# JF-SV-LP0001.net
KiCad netlist of a schematic drawn in EAGLE
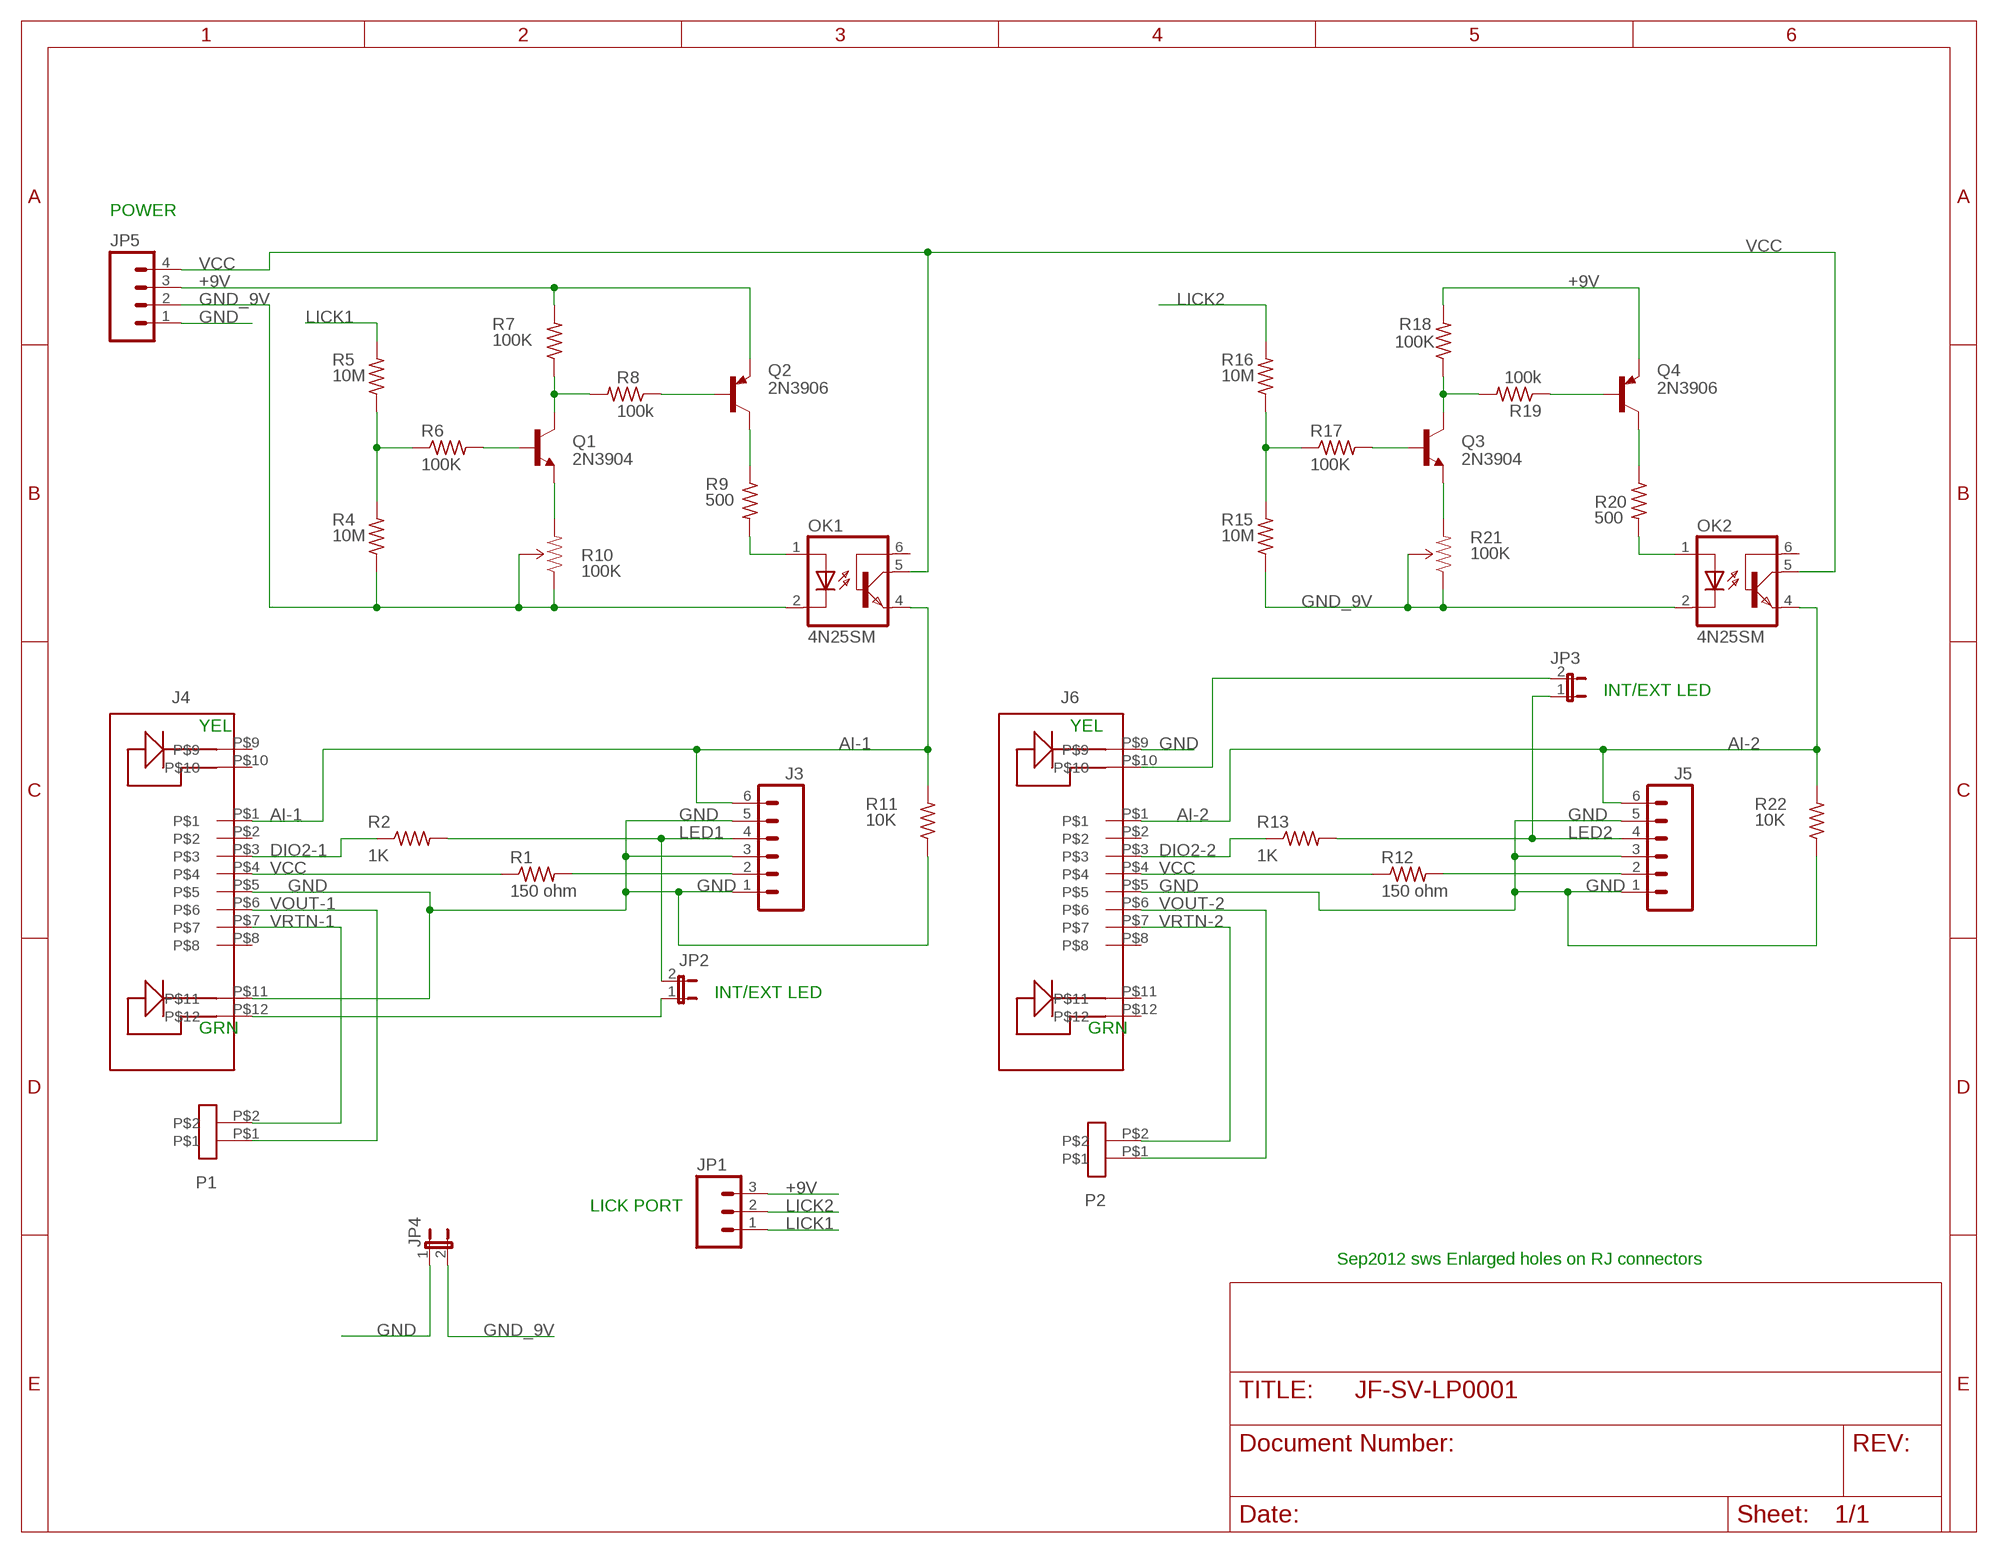
[diagram p0: schematic, sheet 1]

(export (version "E")
  (design (tool "Eeschema 10.0.6"))
  (components
    (comp (ref "J3")
      (value "M063.5MM-6")
      (footprint "eagle-import:SCREWTERMINAL-3.5MM-6")
      (libsource (lib "eagle-import") (part "M063.5MM-6"))
    )
    (comp (ref "J4")
      (value "RJ45_LED")
      (footprint "eagle-import:RJ45_LED")
      (libsource (lib "eagle-import") (part "RJ45_LED"))
    )
    (comp (ref "J5")
      (value "M063.5MM-6")
      (footprint "eagle-import:SCREWTERMINAL-3.5MM-6")
      (libsource (lib "eagle-import") (part "M063.5MM-6"))
    )
    (comp (ref "J6")
      (value "RJ45_LED")
      (footprint "eagle-import:RJ45_LED")
      (libsource (lib "eagle-import") (part "RJ45_LED"))
    )
    (comp (ref "JP1")
      (value "M03POLAR")
      (footprint "eagle-import:MOLEX-1X3")
      (libsource (lib "eagle-import") (part "M03POLAR"))
    )
    (comp (ref "JP2")
      (value "JP1E")
      (footprint "eagle-import:JP1")
      (libsource (lib "eagle-import") (part "JP1E"))
    )
    (comp (ref "JP3")
      (value "JP1E")
      (footprint "eagle-import:JP1")
      (libsource (lib "eagle-import") (part "JP1E"))
    )
    (comp (ref "JP4")
      (value "JUMPER-2PTH")
      (footprint "eagle-import:1X02")
      (libsource (lib "eagle-import") (part "JUMPER-2PTH"))
    )
    (comp (ref "JP5")
      (value "M04POLAR")
      (footprint "eagle-import:MOLEX-1X4")
      (libsource (lib "eagle-import") (part "M04POLAR"))
    )
    (comp (ref "OK1")
      (value "4N25SM")
      (footprint "eagle-import:DIL6-SMD")
      (fields (field (name "MF") "FAIRCHILD SEMICONDUCTOR"))
      (libsource (lib "eagle-import") (part "4N?MS25"))
    )
    (comp (ref "OK2")
      (value "4N25SM")
      (footprint "eagle-import:DIL6-SMD")
      (fields (field (name "MF") "FAIRCHILD SEMICONDUCTOR"))
      (libsource (lib "eagle-import") (part "4N?MS25"))
    )
    (comp (ref "P1")
      (value "CON2MICRO-FIT")
      (footprint "eagle-import:MICRO-FIT-2-RA")
      (libsource (lib "eagle-import") (part "CON2MICRO-FIT"))
    )
    (comp (ref "P2")
      (value "CON2MICRO-FIT")
      (footprint "eagle-import:MICRO-FIT-2-RA")
      (libsource (lib "eagle-import") (part "CON2MICRO-FIT"))
    )
    (comp (ref "Q1")
      (value "2N3904")
      (footprint "eagle-import:SOT23-BEC")
      (libsource (lib "eagle-import") (part "-NPN-SOT23-BECMMBT3904LT1"))
    )
    (comp (ref "Q2")
      (value "2N3906")
      (footprint "eagle-import:SOT23-BEC")
      (libsource (lib "eagle-import") (part "-PNP-SOT23-BECMMBT3906LT1"))
    )
    (comp (ref "Q3")
      (value "2N3904")
      (footprint "eagle-import:SOT23-BEC")
      (libsource (lib "eagle-import") (part "-NPN-SOT23-BECMMBT3904LT1"))
    )
    (comp (ref "Q4")
      (value "2N3906")
      (footprint "eagle-import:SOT23-BEC")
      (libsource (lib "eagle-import") (part "-PNP-SOT23-BECMMBT3906LT1"))
    )
    (comp (ref "R1")
      (value "150 ohm")
      (footprint "eagle-import:0805S")
      (libsource (lib "eagle-import") (part "RESISTOR_SM0805S"))
    )
    (comp (ref "R2")
      (value "1K")
      (footprint "eagle-import:0805S")
      (libsource (lib "eagle-import") (part "RESISTOR_SM0805S"))
    )
    (comp (ref "R4")
      (value "10M")
      (footprint "eagle-import:0805S")
      (libsource (lib "eagle-import") (part "RESISTOR_SM0805S"))
    )
    (comp (ref "R5")
      (value "10M")
      (footprint "eagle-import:0805S")
      (libsource (lib "eagle-import") (part "RESISTOR_SM0805S"))
    )
    (comp (ref "R6")
      (value "100K")
      (footprint "eagle-import:0805S")
      (libsource (lib "eagle-import") (part "RESISTOR_SM0805S"))
    )
    (comp (ref "R7")
      (value "100K")
      (footprint "eagle-import:0805S")
      (libsource (lib "eagle-import") (part "RESISTOR_SM0805S"))
    )
    (comp (ref "R8")
      (value "100k")
      (footprint "eagle-import:0805S")
      (libsource (lib "eagle-import") (part "RESISTOR_SM0805S"))
    )
    (comp (ref "R9")
      (value "500")
      (footprint "eagle-import:0805S")
      (libsource (lib "eagle-import") (part "RESISTOR_SM0805S"))
    )
    (comp (ref "R10")
      (value "100K")
      (footprint "eagle-import:TRIM_POT_PTH")
      (libsource (lib "eagle-import") (part "TRIMPOTPTH"))
    )
    (comp (ref "R11")
      (value "10K")
      (footprint "eagle-import:0805S")
      (libsource (lib "eagle-import") (part "RESISTOR_SM0805S"))
    )
    (comp (ref "R12")
      (value "150 ohm")
      (footprint "eagle-import:0805S")
      (libsource (lib "eagle-import") (part "RESISTOR_SM0805S"))
    )
    (comp (ref "R13")
      (value "1K")
      (footprint "eagle-import:0805S")
      (libsource (lib "eagle-import") (part "RESISTOR_SM0805S"))
    )
    (comp (ref "R15")
      (value "10M")
      (footprint "eagle-import:0805S")
      (libsource (lib "eagle-import") (part "RESISTOR_SM0805S"))
    )
    (comp (ref "R16")
      (value "10M")
      (footprint "eagle-import:0805S")
      (libsource (lib "eagle-import") (part "RESISTOR_SM0805S"))
    )
    (comp (ref "R17")
      (value "100K")
      (footprint "eagle-import:0805S")
      (libsource (lib "eagle-import") (part "RESISTOR_SM0805S"))
    )
    (comp (ref "R18")
      (value "100K")
      (footprint "eagle-import:0805S")
      (libsource (lib "eagle-import") (part "RESISTOR_SM0805S"))
    )
    (comp (ref "R19")
      (value "100k")
      (footprint "eagle-import:0805S")
      (libsource (lib "eagle-import") (part "RESISTOR_SM0805S"))
    )
    (comp (ref "R20")
      (value "500")
      (footprint "eagle-import:0805S")
      (libsource (lib "eagle-import") (part "RESISTOR_SM0805S"))
    )
    (comp (ref "R21")
      (value "100K")
      (footprint "eagle-import:TRIM_POT_PTH")
      (libsource (lib "eagle-import") (part "TRIMPOTPTH"))
    )
    (comp (ref "R22")
      (value "10K")
      (footprint "eagle-import:0805S")
      (libsource (lib "eagle-import") (part "RESISTOR_SM0805S"))
    )
  )
  (nets
    (net (code "1") (name "/+9V") (class "Default")
      (node (ref "JP1") (pin "3") (pinfunction "3_3") (pintype "passive"))
      (node (ref "JP5") (pin "3") (pinfunction "3_3") (pintype "passive"))
      (node (ref "Q2") (pin "E") (pinfunction "E_E") (pintype "passive"))
      (node (ref "Q4") (pin "E") (pinfunction "E_E") (pintype "passive"))
      (node (ref "R18") (pin "2") (pinfunction "2_2") (pintype "passive"))
      (node (ref "R7") (pin "2") (pinfunction "2_2") (pintype "passive"))
    )
    (net (code "2") (name "/AI-1") (class "Default")
      (node (ref "J3") (pin "6") (pinfunction "6_6") (pintype "passive"))
      (node (ref "J4") (pin "P$1") (pinfunction "P$1_P$1") (pintype "bidirectional"))
      (node (ref "OK1") (pin "4") (pinfunction "EMI_4") (pintype "passive"))
      (node (ref "R11") (pin "2") (pinfunction "2_2") (pintype "passive"))
    )
    (net (code "3") (name "/AI-2") (class "Default")
      (node (ref "J5") (pin "6") (pinfunction "6_6") (pintype "passive"))
      (node (ref "J6") (pin "P$1") (pinfunction "P$1_P$1") (pintype "bidirectional"))
      (node (ref "OK2") (pin "4") (pinfunction "EMI_4") (pintype "passive"))
      (node (ref "R22") (pin "2") (pinfunction "2_2") (pintype "passive"))
    )
    (net (code "4") (name "/DIO2-1") (class "Default")
      (node (ref "J4") (pin "P$3") (pinfunction "P$3_P$3") (pintype "bidirectional"))
      (node (ref "R2") (pin "1") (pinfunction "1_1") (pintype "passive"))
    )
    (net (code "5") (name "/DIO2-2") (class "Default")
      (node (ref "J6") (pin "P$3") (pinfunction "P$3_P$3") (pintype "bidirectional"))
      (node (ref "R13") (pin "1") (pinfunction "1_1") (pintype "passive"))
    )
    (net (code "6") (name "/GND") (class "Default")
      (node (ref "J3") (pin "1") (pinfunction "1_1") (pintype "passive"))
      (node (ref "J3") (pin "3") (pinfunction "3_3") (pintype "passive"))
      (node (ref "J3") (pin "5") (pinfunction "5_5") (pintype "passive"))
      (node (ref "J4") (pin "P$11") (pinfunction "P$11_P$11") (pintype "bidirectional"))
      (node (ref "J4") (pin "P$5") (pinfunction "P$5_P$5") (pintype "bidirectional"))
      (node (ref "J5") (pin "1") (pinfunction "1_1") (pintype "passive"))
      (node (ref "J5") (pin "3") (pinfunction "3_3") (pintype "passive"))
      (node (ref "J5") (pin "5") (pinfunction "5_5") (pintype "passive"))
      (node (ref "J6") (pin "P$5") (pinfunction "P$5_P$5") (pintype "bidirectional"))
      (node (ref "J6") (pin "P$9") (pinfunction "P$9_P$9") (pintype "bidirectional"))
      (node (ref "JP4") (pin "1") (pinfunction "1_1") (pintype "passive"))
      (node (ref "JP5") (pin "1") (pinfunction "1_1") (pintype "passive"))
      (node (ref "R11") (pin "1") (pinfunction "1_1") (pintype "passive"))
      (node (ref "R22") (pin "1") (pinfunction "1_1") (pintype "passive"))
    )
    (net (code "7") (name "/GND_9V") (class "Default")
      (node (ref "JP4") (pin "2") (pinfunction "2_2") (pintype "passive"))
      (node (ref "JP5") (pin "2") (pinfunction "2_2") (pintype "passive"))
      (node (ref "OK1") (pin "2") (pinfunction "C_2") (pintype "passive"))
      (node (ref "OK2") (pin "2") (pinfunction "C_2") (pintype "passive"))
      (node (ref "R10") (pin "1") (pinfunction "CCW_1") (pintype "passive"))
      (node (ref "R10") (pin "2") (pinfunction "WIPER_2") (pintype "passive"))
      (node (ref "R15") (pin "1") (pinfunction "1_1") (pintype "passive"))
      (node (ref "R21") (pin "1") (pinfunction "CCW_1") (pintype "passive"))
      (node (ref "R21") (pin "2") (pinfunction "WIPER_2") (pintype "passive"))
      (node (ref "R4") (pin "1") (pinfunction "1_1") (pintype "passive"))
    )
    (net (code "8") (name "/LED1") (class "Default")
      (node (ref "J3") (pin "4") (pinfunction "4_4") (pintype "passive"))
      (node (ref "JP2") (pin "2") (pinfunction "2_2") (pintype "passive"))
      (node (ref "R2") (pin "2") (pinfunction "2_2") (pintype "passive"))
    )
    (net (code "9") (name "/LED2") (class "Default")
      (node (ref "J5") (pin "4") (pinfunction "4_4") (pintype "passive"))
      (node (ref "JP3") (pin "1") (pinfunction "1_1") (pintype "passive"))
      (node (ref "R13") (pin "2") (pinfunction "2_2") (pintype "passive"))
    )
    (net (code "10") (name "/LICK1") (class "Default")
      (node (ref "JP1") (pin "1") (pinfunction "1_1") (pintype "passive"))
      (node (ref "R5") (pin "2") (pinfunction "2_2") (pintype "passive"))
    )
    (net (code "11") (name "/LICK2") (class "Default")
      (node (ref "JP1") (pin "2") (pinfunction "2_2") (pintype "passive"))
      (node (ref "R16") (pin "2") (pinfunction "2_2") (pintype "passive"))
    )
    (net (code "12") (name "/VCC") (class "Default")
      (node (ref "J4") (pin "P$4") (pinfunction "P$4_P$4") (pintype "bidirectional"))
      (node (ref "J6") (pin "P$4") (pinfunction "P$4_P$4") (pintype "bidirectional"))
      (node (ref "JP5") (pin "4") (pinfunction "4_4") (pintype "passive"))
      (node (ref "OK1") (pin "5") (pinfunction "COL_5") (pintype "passive"))
      (node (ref "OK2") (pin "5") (pinfunction "COL_5") (pintype "passive"))
      (node (ref "R1") (pin "1") (pinfunction "1_1") (pintype "passive"))
      (node (ref "R12") (pin "1") (pinfunction "1_1") (pintype "passive"))
    )
    (net (code "13") (name "/VOUT-1") (class "Default")
      (node (ref "J4") (pin "P$6") (pinfunction "P$6_P$6") (pintype "bidirectional"))
      (node (ref "P1") (pin "P$1") (pinfunction "P$1_P$1") (pintype "bidirectional"))
    )
    (net (code "14") (name "/VOUT-2") (class "Default")
      (node (ref "J6") (pin "P$6") (pinfunction "P$6_P$6") (pintype "bidirectional"))
      (node (ref "P2") (pin "P$1") (pinfunction "P$1_P$1") (pintype "bidirectional"))
    )
    (net (code "15") (name "/VRTN-1") (class "Default")
      (node (ref "J4") (pin "P$7") (pinfunction "P$7_P$7") (pintype "bidirectional"))
      (node (ref "P1") (pin "P$2") (pinfunction "P$2_P$2") (pintype "bidirectional"))
    )
    (net (code "16") (name "/VRTN-2") (class "Default")
      (node (ref "J6") (pin "P$7") (pinfunction "P$7_P$7") (pintype "bidirectional"))
      (node (ref "P2") (pin "P$2") (pinfunction "P$2_P$2") (pintype "bidirectional"))
    )
    (net (code "17") (name "Net-(J3-Pad2)") (class "Default")
      (node (ref "J3") (pin "2") (pinfunction "2_2") (pintype "passive"))
      (node (ref "R1") (pin "2") (pinfunction "2_2") (pintype "passive"))
    )
    (net (code "18") (name "Net-(J4-PadP$12)") (class "Default")
      (node (ref "J4") (pin "P$12") (pinfunction "P$12_P$12") (pintype "bidirectional"))
      (node (ref "JP2") (pin "1") (pinfunction "1_1") (pintype "passive"))
    )
    (net (code "19") (name "Net-(J5-Pad2)") (class "Default")
      (node (ref "J5") (pin "2") (pinfunction "2_2") (pintype "passive"))
      (node (ref "R12") (pin "2") (pinfunction "2_2") (pintype "passive"))
    )
    (net (code "20") (name "Net-(J6-PadP$10)") (class "Default")
      (node (ref "J6") (pin "P$10") (pinfunction "P$10_P$10") (pintype "bidirectional"))
      (node (ref "JP3") (pin "2") (pinfunction "2_2") (pintype "passive"))
    )
    (net (code "21") (name "Net-(OK1-A)") (class "Default")
      (node (ref "OK1") (pin "1") (pinfunction "A_1") (pintype "passive"))
      (node (ref "R9") (pin "2") (pinfunction "2_2") (pintype "passive"))
    )
    (net (code "22") (name "Net-(OK2-A)") (class "Default")
      (node (ref "OK2") (pin "1") (pinfunction "A_1") (pintype "passive"))
      (node (ref "R20") (pin "2") (pinfunction "2_2") (pintype "passive"))
    )
    (net (code "23") (name "Net-(Q1-PadB)") (class "Default")
      (node (ref "Q1") (pin "B") (pinfunction "B_B") (pintype "passive"))
      (node (ref "R6") (pin "2") (pinfunction "2_2") (pintype "passive"))
    )
    (net (code "24") (name "Net-(Q1-PadC)") (class "Default")
      (node (ref "Q1") (pin "C") (pinfunction "C_C") (pintype "passive"))
      (node (ref "R7") (pin "1") (pinfunction "1_1") (pintype "passive"))
      (node (ref "R8") (pin "2") (pinfunction "2_2") (pintype "passive"))
    )
    (net (code "25") (name "Net-(Q2-PadB)") (class "Default")
      (node (ref "Q2") (pin "B") (pinfunction "B_B") (pintype "passive"))
      (node (ref "R8") (pin "1") (pinfunction "1_1") (pintype "passive"))
    )
    (net (code "26") (name "Net-(Q2-PadC)") (class "Default")
      (node (ref "Q2") (pin "C") (pinfunction "C_C") (pintype "passive"))
      (node (ref "R9") (pin "1") (pinfunction "1_1") (pintype "passive"))
    )
    (net (code "27") (name "Net-(Q3-PadB)") (class "Default")
      (node (ref "Q3") (pin "B") (pinfunction "B_B") (pintype "passive"))
      (node (ref "R17") (pin "2") (pinfunction "2_2") (pintype "passive"))
    )
    (net (code "28") (name "Net-(Q3-PadC)") (class "Default")
      (node (ref "Q3") (pin "C") (pinfunction "C_C") (pintype "passive"))
      (node (ref "R18") (pin "1") (pinfunction "1_1") (pintype "passive"))
      (node (ref "R19") (pin "2") (pinfunction "2_2") (pintype "passive"))
    )
    (net (code "29") (name "Net-(Q4-PadB)") (class "Default")
      (node (ref "Q4") (pin "B") (pinfunction "B_B") (pintype "passive"))
      (node (ref "R19") (pin "1") (pinfunction "1_1") (pintype "passive"))
    )
    (net (code "30") (name "Net-(Q4-PadC)") (class "Default")
      (node (ref "Q4") (pin "C") (pinfunction "C_C") (pintype "passive"))
      (node (ref "R20") (pin "1") (pinfunction "1_1") (pintype "passive"))
    )
    (net (code "31") (name "Net-(R4-Pad2)") (class "Default")
      (node (ref "R4") (pin "2") (pinfunction "2_2") (pintype "passive"))
      (node (ref "R5") (pin "1") (pinfunction "1_1") (pintype "passive"))
      (node (ref "R6") (pin "1") (pinfunction "1_1") (pintype "passive"))
    )
    (net (code "32") (name "Net-(R10-CW)") (class "Default")
      (node (ref "Q1") (pin "E") (pinfunction "E_E") (pintype "passive"))
      (node (ref "R10") (pin "3") (pinfunction "CW_3") (pintype "passive"))
    )
    (net (code "33") (name "Net-(R15-Pad2)") (class "Default")
      (node (ref "R15") (pin "2") (pinfunction "2_2") (pintype "passive"))
      (node (ref "R16") (pin "1") (pinfunction "1_1") (pintype "passive"))
      (node (ref "R17") (pin "1") (pinfunction "1_1") (pintype "passive"))
    )
    (net (code "34") (name "Net-(R21-CW)") (class "Default")
      (node (ref "Q3") (pin "E") (pinfunction "E_E") (pintype "passive"))
      (node (ref "R21") (pin "3") (pinfunction "CW_3") (pintype "passive"))
    )
    (net (code "35") (name "unconnected-(J4-PadP$2)") (class "Default")
      (node (ref "J4") (pin "P$2") (pinfunction "P$2_P$2") (pintype "bidirectional"))
    )
    (net (code "36") (name "unconnected-(J4-PadP$8)") (class "Default")
      (node (ref "J4") (pin "P$8") (pinfunction "P$8_P$8") (pintype "bidirectional"))
    )
    (net (code "37") (name "unconnected-(J4-PadP$9)") (class "Default")
      (node (ref "J4") (pin "P$9") (pinfunction "P$9_P$9") (pintype "bidirectional"))
    )
    (net (code "38") (name "unconnected-(J4-PadP$10)") (class "Default")
      (node (ref "J4") (pin "P$10") (pinfunction "P$10_P$10") (pintype "bidirectional"))
    )
    (net (code "39") (name "unconnected-(J6-PadP$2)") (class "Default")
      (node (ref "J6") (pin "P$2") (pinfunction "P$2_P$2") (pintype "bidirectional"))
    )
    (net (code "40") (name "unconnected-(J6-PadP$8)") (class "Default")
      (node (ref "J6") (pin "P$8") (pinfunction "P$8_P$8") (pintype "bidirectional"))
    )
    (net (code "41") (name "unconnected-(J6-PadP$11)") (class "Default")
      (node (ref "J6") (pin "P$11") (pinfunction "P$11_P$11") (pintype "bidirectional"))
    )
    (net (code "42") (name "unconnected-(J6-PadP$12)") (class "Default")
      (node (ref "J6") (pin "P$12") (pinfunction "P$12_P$12") (pintype "bidirectional"))
    )
    (net (code "43") (name "unconnected-(OK1-BAS-Pad6)") (class "Default")
      (node (ref "OK1") (pin "6") (pinfunction "BAS_6") (pintype "passive"))
    )
    (net (code "44") (name "unconnected-(OK2-BAS-Pad6)") (class "Default")
      (node (ref "OK2") (pin "6") (pinfunction "BAS_6") (pintype "passive"))
    )
  )
)
